# REMOTER.net
KiCad netlist of a schematic drawn in Altium Designer
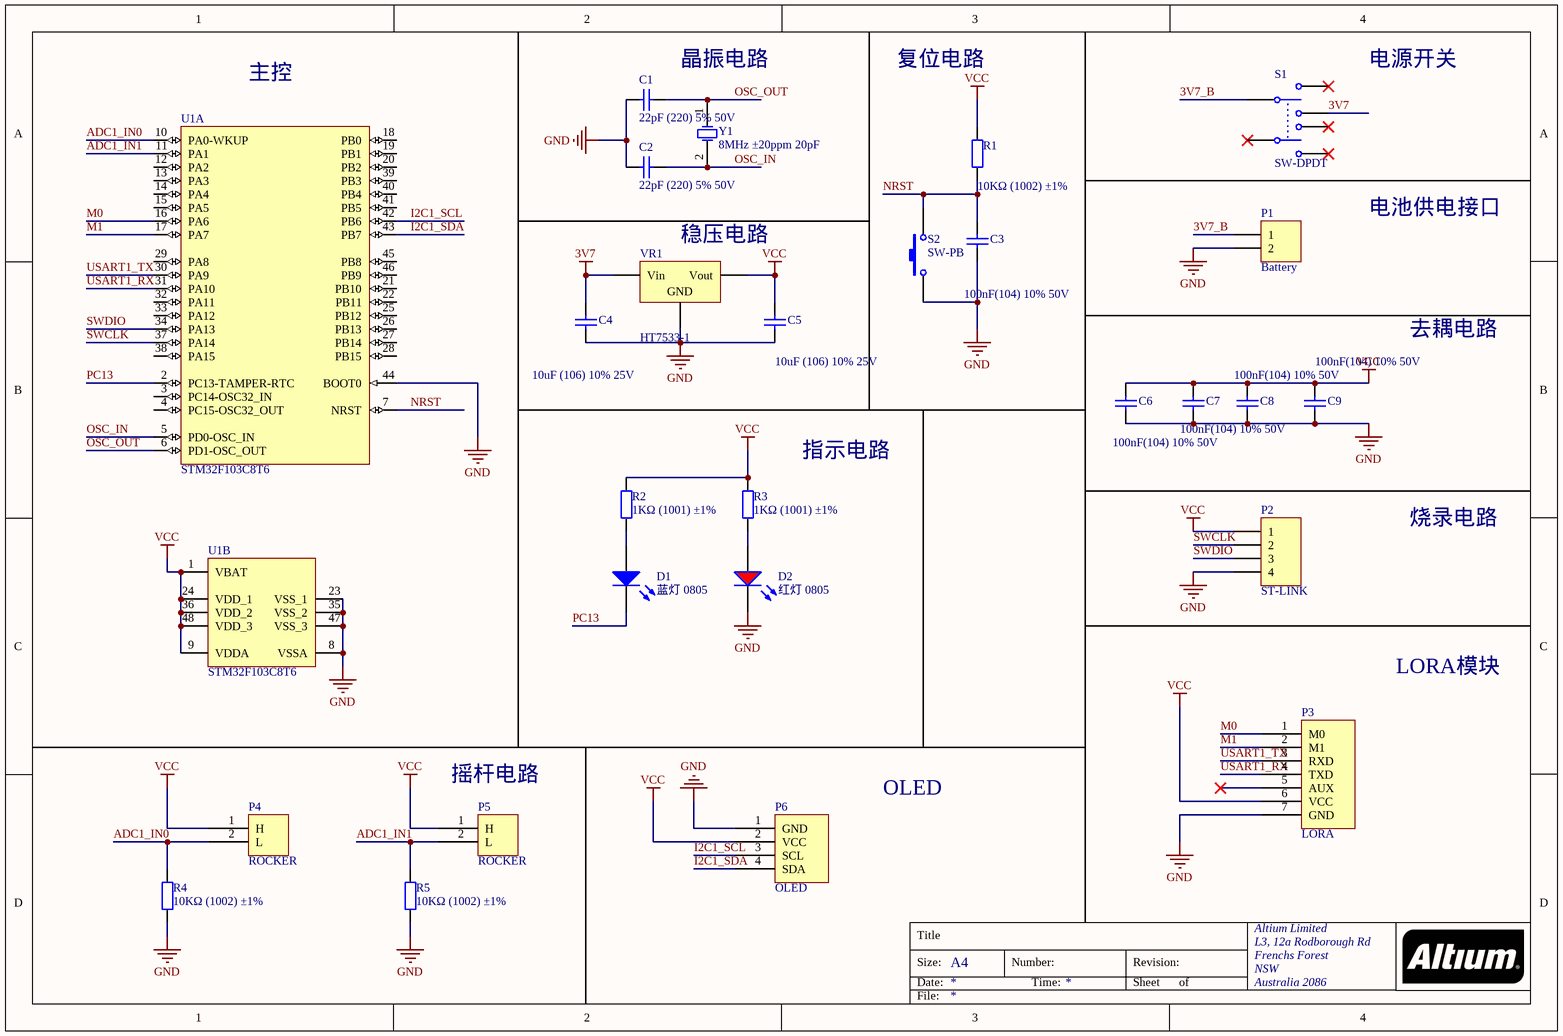
[diagram p0: REMOTER.SchDoc]

(export (version "E")
  (design (tool "Eeschema 10.0.6"))
  (components
    (comp (ref "C1")
      (value "22pF (220) 5% 50V")
      (footprint "0805_C")
      (description "贴片电容")
      (libsource (lib "Miscellaneous Devices LC") (part "0805 22pF (220) 5% 50V"))
    )
    (comp (ref "C2")
      (value "22pF (220) 5% 50V")
      (footprint "0805_C")
      (description "贴片电容")
      (libsource (lib "Miscellaneous Devices LC") (part "0805 22pF (220) 5% 50V"))
    )
    (comp (ref "C3")
      (value "100nF(104) 10% 50V")
      (footprint "0805_C")
      (description "贴片电容")
      (libsource (lib "Miscellaneous Devices LC") (part "0805 100nF(104) 10% 50V"))
    )
    (comp (ref "C4")
      (value "10uF (106) 10% 25V")
      (footprint "0805_C")
      (description "贴片电容")
      (libsource (lib "Miscellaneous Devices LC") (part "0805 10uF (106) 10% 25V"))
    )
    (comp (ref "C5")
      (value "10uF (106) 10% 25V")
      (footprint "0805_C")
      (description "贴片电容")
      (libsource (lib "Miscellaneous Devices LC") (part "0805 10uF (106) 10% 25V"))
    )
    (comp (ref "C6")
      (value "100nF(104) 10% 50V")
      (footprint "0805_C")
      (description "贴片电容")
      (libsource (lib "Miscellaneous Devices LC") (part "0805 100nF(104) 10% 50V"))
    )
    (comp (ref "C7")
      (value "100nF(104) 10% 50V")
      (footprint "0805_C")
      (description "贴片电容")
      (libsource (lib "Miscellaneous Devices LC") (part "0805 100nF(104) 10% 50V"))
    )
    (comp (ref "C8")
      (value "100nF(104) 10% 50V")
      (footprint "0805_C")
      (description "贴片电容")
      (libsource (lib "Miscellaneous Devices LC") (part "0805 100nF(104) 10% 50V"))
    )
    (comp (ref "C9")
      (value "100nF(104) 10% 50V")
      (footprint "0805_C")
      (description "贴片电容")
      (libsource (lib "Miscellaneous Devices LC") (part "0805 100nF(104) 10% 50V"))
    )
    (comp (ref "D1")
      (value "蓝灯 0805")
      (footprint "0805_LED_S1")
      (description "发光二极管")
      (libsource (lib "Miscellaneous Devices LC") (part "0805 蓝灯"))
    )
    (comp (ref "D2")
      (value "红灯 0805")
      (footprint "0805_LED_S1")
      (description "发光二极管")
      (libsource (lib "Miscellaneous Devices LC") (part "0805 红灯"))
    )
    (comp (ref "P1")
      (value "Battery")
      (footprint "HDR1X2")
      (description "Header, 2-Pin")
      (fields (field (name "PUBLISHER") "Altium Limited"))
      (libsource (lib "Miscellaneous Connectors") (part "Header 2"))
    )
    (comp (ref "P2")
      (value "ST-LINK")
      (footprint "HDR1X4")
      (description "Header, 4-Pin")
      (fields (field (name "PUBLISHER") "Altium Limited"))
      (libsource (lib "Miscellaneous Connectors") (part "Header 4"))
    )
    (comp (ref "P3") (value "LORA") (footprint "LORA") (libsource (lib "REMOTER") (part "LORA")))
    (comp (ref "P4") (value "ROCKER") (footprint "ROCKER") (libsource (lib "REMOTER") (part "ROCKER")))
    (comp (ref "P5") (value "ROCKER") (footprint "ROCKER") (libsource (lib "REMOTER") (part "ROCKER")))
    (comp (ref "P6") (value "OLED") (footprint "OLED") (libsource (lib "REMOTER") (part "OLED")))
    (comp (ref "R1")
      (value "10KΩ (1002) ±1%")
      (footprint "0805_R")
      (description "贴片电阻")
      (libsource (lib "") (part "0805 10KΩ (1002) 1%_1"))
    )
    (comp (ref "R2")
      (value "1KΩ (1001) ±1%")
      (footprint "0805_R")
      (description "贴片电阻")
      (libsource (lib "Miscellaneous Devices LC") (part "0805 1KΩ (1001) 1%"))
    )
    (comp (ref "R3")
      (value "1KΩ (1001) ±1%")
      (footprint "0805_R")
      (description "贴片电阻")
      (libsource (lib "Miscellaneous Devices LC") (part "0805 1KΩ (1001) 1%"))
    )
    (comp (ref "R4")
      (value "10KΩ (1002) ±1%")
      (footprint "0805_R")
      (description "贴片电阻")
      (libsource (lib "Miscellaneous Devices LC") (part "0805 10KΩ (1002) 1%"))
    )
    (comp (ref "R5")
      (value "10KΩ (1002) ±1%")
      (footprint "0805_R")
      (description "贴片电阻")
      (libsource (lib "Miscellaneous Devices LC") (part "0805 10KΩ (1002) 1%"))
    )
    (comp (ref "S1")
      (value "SW-DPDT")
      (footprint "DPDT-6")
      (description "Double-Pole, Double-Throw Switch")
      (fields (field (name "PUBLISHER") "Altium Limited"))
      (libsource (lib "Miscellaneous Devices") (part "SW-DPDT"))
    )
    (comp (ref "S2")
      (value "SW-PB")
      (footprint "SPST-2")
      (description "Switch")
      (fields (field (name "PUBLISHER") "Altium Limited"))
      (libsource (lib "Miscellaneous Devices") (part "SW-PB"))
    )
    (comp (ref "U1")
      (value "STM32F103C8T6")
      (footprint "LQFP-48_7x7x05P")
      (libsource (lib "STMicroelectronics STM32 F1") (part "STM32F103C8T6"))
    )
    (comp (ref "VR1")
      (value "HT7533-1")
      (footprint "SOT-89(SOT-89-3)")
      (description "低压差线性稳压(LDO)")
      (libsource (lib "Miscellaneous Devices LC") (part "SOT-89 HT7533-1"))
    )
    (comp (ref "Y1")
      (value "8MHz ±20ppm 20pF")
      (footprint "SMD-5032_2P")
      (description "贴片晶振")
      (libsource (lib "Miscellaneous Devices LC") (part "SMD-5032_2P 8MHz 20ppm 20pF"))
    )
  )
  (nets
    (net (code "1") (name "/3V7_B") (class "Default")
      (node (ref "P1") (pin "1") (pinfunction "1_1") (pintype "passive"))
      (node (ref "S1") (pin "1") (pinfunction "1_1") (pintype "passive"))
    )
    (net (code "2") (name "/ADC1_IN0") (class "Default")
      (node (ref "P4") (pin "2") (pinfunction "L_2") (pintype "passive"))
      (node (ref "R4") (pin "2") (pinfunction "2_2") (pintype "passive"))
      (node (ref "U1") (pin "10") (pinfunction "PA0-WKUP_10") (pintype "bidirectional"))
    )
    (net (code "3") (name "/ADC1_IN1") (class "Default")
      (node (ref "P5") (pin "2") (pinfunction "L_2") (pintype "passive"))
      (node (ref "R5") (pin "2") (pinfunction "2_2") (pintype "passive"))
      (node (ref "U1") (pin "11") (pinfunction "PA1_11") (pintype "bidirectional"))
    )
    (net (code "4") (name "/I2C1_SCL") (class "Default")
      (node (ref "P6") (pin "3") (pinfunction "SCL_3") (pintype "passive"))
      (node (ref "U1") (pin "42") (pinfunction "PB6_42") (pintype "bidirectional"))
    )
    (net (code "5") (name "/I2C1_SDA") (class "Default")
      (node (ref "P6") (pin "4") (pinfunction "SDA_4") (pintype "passive"))
      (node (ref "U1") (pin "43") (pinfunction "PB7_43") (pintype "bidirectional"))
    )
    (net (code "6") (name "/M0") (class "Default")
      (node (ref "P3") (pin "1") (pinfunction "M0_1") (pintype "passive"))
      (node (ref "U1") (pin "16") (pinfunction "PA6_16") (pintype "bidirectional"))
    )
    (net (code "7") (name "/M1") (class "Default")
      (node (ref "P3") (pin "2") (pinfunction "M1_2") (pintype "passive"))
      (node (ref "U1") (pin "17") (pinfunction "PA7_17") (pintype "bidirectional"))
    )
    (net (code "8") (name "/NRST") (class "Default")
      (node (ref "C3") (pin "2") (pinfunction "2_2") (pintype "passive"))
      (node (ref "R1") (pin "2") (pinfunction "2_2") (pintype "passive"))
      (node (ref "S2") (pin "2") (pinfunction "2_2") (pintype "passive"))
      (node (ref "U1") (pin "7") (pinfunction "NRST_7") (pintype "bidirectional"))
    )
    (net (code "9") (name "/OSC_IN") (class "Default")
      (node (ref "C2") (pin "2") (pinfunction "2_2") (pintype "passive"))
      (node (ref "U1") (pin "5") (pinfunction "PD0-OSC_IN_5") (pintype "bidirectional"))
      (node (ref "Y1") (pin "2") (pinfunction "OSC2_2") (pintype "passive"))
    )
    (net (code "10") (name "/OSC_OUT") (class "Default")
      (node (ref "C1") (pin "2") (pinfunction "2_2") (pintype "passive"))
      (node (ref "U1") (pin "6") (pinfunction "PD1-OSC_OUT_6") (pintype "bidirectional"))
      (node (ref "Y1") (pin "1") (pinfunction "OSC1_1") (pintype "passive"))
    )
    (net (code "11") (name "/PC13") (class "Default")
      (node (ref "D1") (pin "K") (pinfunction "K_K") (pintype "passive"))
      (node (ref "U1") (pin "2") (pinfunction "PC13-TAMPER-RTC_2") (pintype "bidirectional"))
    )
    (net (code "12") (name "/SWCLK") (class "Default")
      (node (ref "P2") (pin "2") (pinfunction "2_2") (pintype "passive"))
      (node (ref "U1") (pin "37") (pinfunction "PA14_37") (pintype "bidirectional"))
    )
    (net (code "13") (name "/SWDIO") (class "Default")
      (node (ref "P2") (pin "3") (pinfunction "3_3") (pintype "passive"))
      (node (ref "U1") (pin "34") (pinfunction "PA13_34") (pintype "bidirectional"))
    )
    (net (code "14") (name "/USART1_RX") (class "Default")
      (node (ref "P3") (pin "4") (pinfunction "TXD_4") (pintype "passive"))
      (node (ref "U1") (pin "31") (pinfunction "PA10_31") (pintype "bidirectional"))
    )
    (net (code "15") (name "/USART1_TX") (class "Default")
      (node (ref "P3") (pin "3") (pinfunction "RXD_3") (pintype "passive"))
      (node (ref "U1") (pin "30") (pinfunction "PA9_30") (pintype "bidirectional"))
    )
    (net (code "16") (name "3V7") (class "Default")
      (node (ref "C4") (pin "2") (pinfunction "2_2") (pintype "passive"))
      (node (ref "S1") (pin "3") (pinfunction "3_3") (pintype "passive"))
      (node (ref "VR1") (pin "2") (pinfunction "Vin_2") (pintype "passive"))
    )
    (net (code "17") (name "GND") (class "Default")
      (node (ref "C1") (pin "1") (pinfunction "1_1") (pintype "passive"))
      (node (ref "C2") (pin "1") (pinfunction "1_1") (pintype "passive"))
      (node (ref "C3") (pin "1") (pinfunction "1_1") (pintype "passive"))
      (node (ref "C4") (pin "1") (pinfunction "1_1") (pintype "passive"))
      (node (ref "C5") (pin "2") (pinfunction "2_2") (pintype "passive"))
      (node (ref "C6") (pin "1") (pinfunction "1_1") (pintype "passive"))
      (node (ref "C7") (pin "1") (pinfunction "1_1") (pintype "passive"))
      (node (ref "C8") (pin "1") (pinfunction "1_1") (pintype "passive"))
      (node (ref "C9") (pin "1") (pinfunction "1_1") (pintype "passive"))
      (node (ref "D2") (pin "K") (pinfunction "K_K") (pintype "passive"))
      (node (ref "P1") (pin "2") (pinfunction "2_2") (pintype "passive"))
      (node (ref "P2") (pin "4") (pinfunction "4_4") (pintype "passive"))
      (node (ref "P3") (pin "7") (pinfunction "GND_7") (pintype "passive"))
      (node (ref "P6") (pin "1") (pinfunction "GND_1") (pintype "passive"))
      (node (ref "R4") (pin "1") (pinfunction "1_1") (pintype "passive"))
      (node (ref "R5") (pin "1") (pinfunction "1_1") (pintype "passive"))
      (node (ref "S2") (pin "1") (pinfunction "1_1") (pintype "passive"))
      (node (ref "U1") (pin "23") (pinfunction "VSS_1_23") (pintype "power_in"))
      (node (ref "U1") (pin "35") (pinfunction "VSS_2_35") (pintype "power_in"))
      (node (ref "U1") (pin "44") (pinfunction "BOOT0_44") (pintype "input"))
      (node (ref "U1") (pin "47") (pinfunction "VSS_3_47") (pintype "power_in"))
      (node (ref "U1") (pin "8") (pinfunction "VSSA_8") (pintype "power_in"))
      (node (ref "VR1") (pin "1") (pinfunction "GND_1") (pintype "passive"))
    )
    (net (code "18") (name "Net-(D1-PadA)") (class "Default")
      (node (ref "D1") (pin "A") (pinfunction "A_A") (pintype "passive"))
      (node (ref "R2") (pin "2") (pinfunction "2_2") (pintype "passive"))
    )
    (net (code "19") (name "Net-(D2-PadA)") (class "Default")
      (node (ref "D2") (pin "A") (pinfunction "A_A") (pintype "passive"))
      (node (ref "R3") (pin "2") (pinfunction "2_2") (pintype "passive"))
    )
    (net (code "20") (name "VCC") (class "Default")
      (node (ref "C5") (pin "1") (pinfunction "1_1") (pintype "passive"))
      (node (ref "C6") (pin "2") (pinfunction "2_2") (pintype "passive"))
      (node (ref "C7") (pin "2") (pinfunction "2_2") (pintype "passive"))
      (node (ref "C8") (pin "2") (pinfunction "2_2") (pintype "passive"))
      (node (ref "C9") (pin "2") (pinfunction "2_2") (pintype "passive"))
      (node (ref "P2") (pin "1") (pinfunction "1_1") (pintype "passive"))
      (node (ref "P3") (pin "6") (pinfunction "VCC_6") (pintype "passive"))
      (node (ref "P4") (pin "1") (pinfunction "H_1") (pintype "passive"))
      (node (ref "P5") (pin "1") (pinfunction "H_1") (pintype "passive"))
      (node (ref "P6") (pin "2") (pinfunction "VCC_2") (pintype "passive"))
      (node (ref "R1") (pin "1") (pinfunction "1_1") (pintype "passive"))
      (node (ref "R2") (pin "1") (pinfunction "1_1") (pintype "passive"))
      (node (ref "R3") (pin "1") (pinfunction "1_1") (pintype "passive"))
      (node (ref "U1") (pin "1") (pinfunction "VBAT_1") (pintype "power_in"))
      (node (ref "U1") (pin "24") (pinfunction "VDD_1_24") (pintype "power_in"))
      (node (ref "U1") (pin "36") (pinfunction "VDD_2_36") (pintype "power_in"))
      (node (ref "U1") (pin "48") (pinfunction "VDD_3_48") (pintype "power_in"))
      (node (ref "U1") (pin "9") (pinfunction "VDDA_9") (pintype "power_in"))
      (node (ref "VR1") (pin "3") (pinfunction "Vout_3") (pintype "passive"))
    )
    (net (code "21") (name "unconnected-(P3-AUX-Pad5)") (class "Default")
      (node (ref "P3") (pin "5") (pinfunction "AUX_5") (pintype "passive+no_connect"))
    )
    (net (code "22") (name "unconnected-(S1-Pad2)") (class "Default")
      (node (ref "S1") (pin "2") (pinfunction "2_2") (pintype "passive+no_connect"))
    )
    (net (code "23") (name "unconnected-(S1-Pad4)") (class "Default")
      (node (ref "S1") (pin "4") (pinfunction "4_4") (pintype "passive+no_connect"))
    )
    (net (code "24") (name "unconnected-(S1-Pad5)") (class "Default")
      (node (ref "S1") (pin "5") (pinfunction "5_5") (pintype "passive+no_connect"))
    )
    (net (code "25") (name "unconnected-(S1-Pad6)") (class "Default")
      (node (ref "S1") (pin "6") (pinfunction "6_6") (pintype "passive+no_connect"))
    )
    (net (code "26") (name "unconnected-(U1A-PA2-Pad12)") (class "Default")
      (node (ref "U1") (pin "12") (pinfunction "PA2_12") (pintype "bidirectional"))
    )
    (net (code "27") (name "unconnected-(U1A-PA3-Pad13)") (class "Default")
      (node (ref "U1") (pin "13") (pinfunction "PA3_13") (pintype "bidirectional"))
    )
    (net (code "28") (name "unconnected-(U1A-PA4-Pad14)") (class "Default")
      (node (ref "U1") (pin "14") (pinfunction "PA4_14") (pintype "bidirectional"))
    )
    (net (code "29") (name "unconnected-(U1A-PA5-Pad15)") (class "Default")
      (node (ref "U1") (pin "15") (pinfunction "PA5_15") (pintype "bidirectional"))
    )
    (net (code "30") (name "unconnected-(U1A-PA8-Pad29)") (class "Default")
      (node (ref "U1") (pin "29") (pinfunction "PA8_29") (pintype "bidirectional"))
    )
    (net (code "31") (name "unconnected-(U1A-PA11-Pad32)") (class "Default")
      (node (ref "U1") (pin "32") (pinfunction "PA11_32") (pintype "bidirectional"))
    )
    (net (code "32") (name "unconnected-(U1A-PA12-Pad33)") (class "Default")
      (node (ref "U1") (pin "33") (pinfunction "PA12_33") (pintype "bidirectional"))
    )
    (net (code "33") (name "unconnected-(U1A-PA15-Pad38)") (class "Default")
      (node (ref "U1") (pin "38") (pinfunction "PA15_38") (pintype "bidirectional"))
    )
    (net (code "34") (name "unconnected-(U1A-PB0-Pad18)") (class "Default")
      (node (ref "U1") (pin "18") (pinfunction "PB0_18") (pintype "bidirectional"))
    )
    (net (code "35") (name "unconnected-(U1A-PB1-Pad19)") (class "Default")
      (node (ref "U1") (pin "19") (pinfunction "PB1_19") (pintype "bidirectional"))
    )
    (net (code "36") (name "unconnected-(U1A-PB2-Pad20)") (class "Default")
      (node (ref "U1") (pin "20") (pinfunction "PB2_20") (pintype "bidirectional"))
    )
    (net (code "37") (name "unconnected-(U1A-PB3-Pad39)") (class "Default")
      (node (ref "U1") (pin "39") (pinfunction "PB3_39") (pintype "bidirectional"))
    )
    (net (code "38") (name "unconnected-(U1A-PB4-Pad40)") (class "Default")
      (node (ref "U1") (pin "40") (pinfunction "PB4_40") (pintype "bidirectional"))
    )
    (net (code "39") (name "unconnected-(U1A-PB5-Pad41)") (class "Default")
      (node (ref "U1") (pin "41") (pinfunction "PB5_41") (pintype "bidirectional"))
    )
    (net (code "40") (name "unconnected-(U1A-PB8-Pad45)") (class "Default")
      (node (ref "U1") (pin "45") (pinfunction "PB8_45") (pintype "bidirectional"))
    )
    (net (code "41") (name "unconnected-(U1A-PB9-Pad46)") (class "Default")
      (node (ref "U1") (pin "46") (pinfunction "PB9_46") (pintype "bidirectional"))
    )
    (net (code "42") (name "unconnected-(U1A-PB10-Pad21)") (class "Default")
      (node (ref "U1") (pin "21") (pinfunction "PB10_21") (pintype "bidirectional"))
    )
    (net (code "43") (name "unconnected-(U1A-PB11-Pad22)") (class "Default")
      (node (ref "U1") (pin "22") (pinfunction "PB11_22") (pintype "bidirectional"))
    )
    (net (code "44") (name "unconnected-(U1A-PB12-Pad25)") (class "Default")
      (node (ref "U1") (pin "25") (pinfunction "PB12_25") (pintype "bidirectional"))
    )
    (net (code "45") (name "unconnected-(U1A-PB13-Pad26)") (class "Default")
      (node (ref "U1") (pin "26") (pinfunction "PB13_26") (pintype "bidirectional"))
    )
    (net (code "46") (name "unconnected-(U1A-PB14-Pad27)") (class "Default")
      (node (ref "U1") (pin "27") (pinfunction "PB14_27") (pintype "bidirectional"))
    )
    (net (code "47") (name "unconnected-(U1A-PB15-Pad28)") (class "Default")
      (node (ref "U1") (pin "28") (pinfunction "PB15_28") (pintype "bidirectional"))
    )
    (net (code "48") (name "unconnected-(U1A-PC14-OSC32_IN-Pad3)") (class "Default")
      (node (ref "U1") (pin "3") (pinfunction "PC14-OSC32_IN_3") (pintype "bidirectional"))
    )
    (net (code "49") (name "unconnected-(U1A-PC15-OSC32_OUT-Pad4)") (class "Default")
      (node (ref "U1") (pin "4") (pinfunction "PC15-OSC32_OUT_4") (pintype "bidirectional"))
    )
  )
)
